# design.net
KiCad netlist of a schematic drawn in Altium Designer
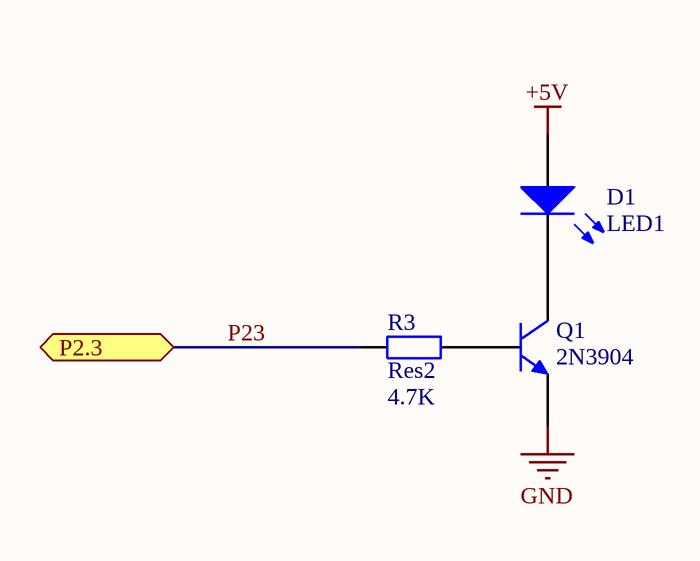
[diagram p0: 红外发射模块.SchDoc]

(export (version "E")
  (design (tool "Eeschema 10.0.6"))
  (components
    (comp (ref "D1")
      (value "LED1")
      (footprint "LED-1")
      (description "Typical RED GaAs LED")
      (fields (field (name "PUBLISHER") "Altium Limited"))
      (libsource (lib "Miscellaneous Devices") (part "LED1"))
    )
    (comp (ref "Q1")
      (value "2N3904")
      (footprint "TO-92A")
      (description "NPN General Purpose Amplifier")
      (fields (field (name "PUBLISHER") "Altium Limited"))
      (libsource (lib "Miscellaneous Devices") (part "2N3904"))
    )
    (comp (ref "R3")
      (value "Res2")
      (footprint "AXIAL-0.4")
      (description "Resistor")
      (fields (field (name "ALTIUM_VALUE") "4.7K") (field (name "PUBLISHER") "Altium Limited"))
      (libsource (lib "Miscellaneous Devices") (part "Res2"))
    )
  )
  (nets
    (net (code "1") (name "+5V") (class "Default")
      (node (ref "D1") (pin "1") (pinfunction "A_1") (pintype "passive"))
    )
    (net (code "2") (name "/P23") (class "Default")
      (node (ref "R3") (pin "1") (pinfunction "1_1") (pintype "passive"))
    )
    (net (code "3") (name "GND") (class "Default")
      (node (ref "Q1") (pin "1") (pinfunction "E_1") (pintype "passive"))
    )
    (net (code "4") (name "Net-(D1-K)") (class "Default")
      (node (ref "D1") (pin "2") (pinfunction "K_2") (pintype "passive"))
      (node (ref "Q1") (pin "3") (pinfunction "C_3") (pintype "passive"))
    )
    (net (code "5") (name "Net-(Q1-B)") (class "Default")
      (node (ref "Q1") (pin "2") (pinfunction "B_2") (pintype "passive"))
      (node (ref "R3") (pin "2") (pinfunction "2_2") (pintype "passive"))
    )
  )
)
